# OledAdapter.net
KiCad netlist of a schematic drawn in EAGLE
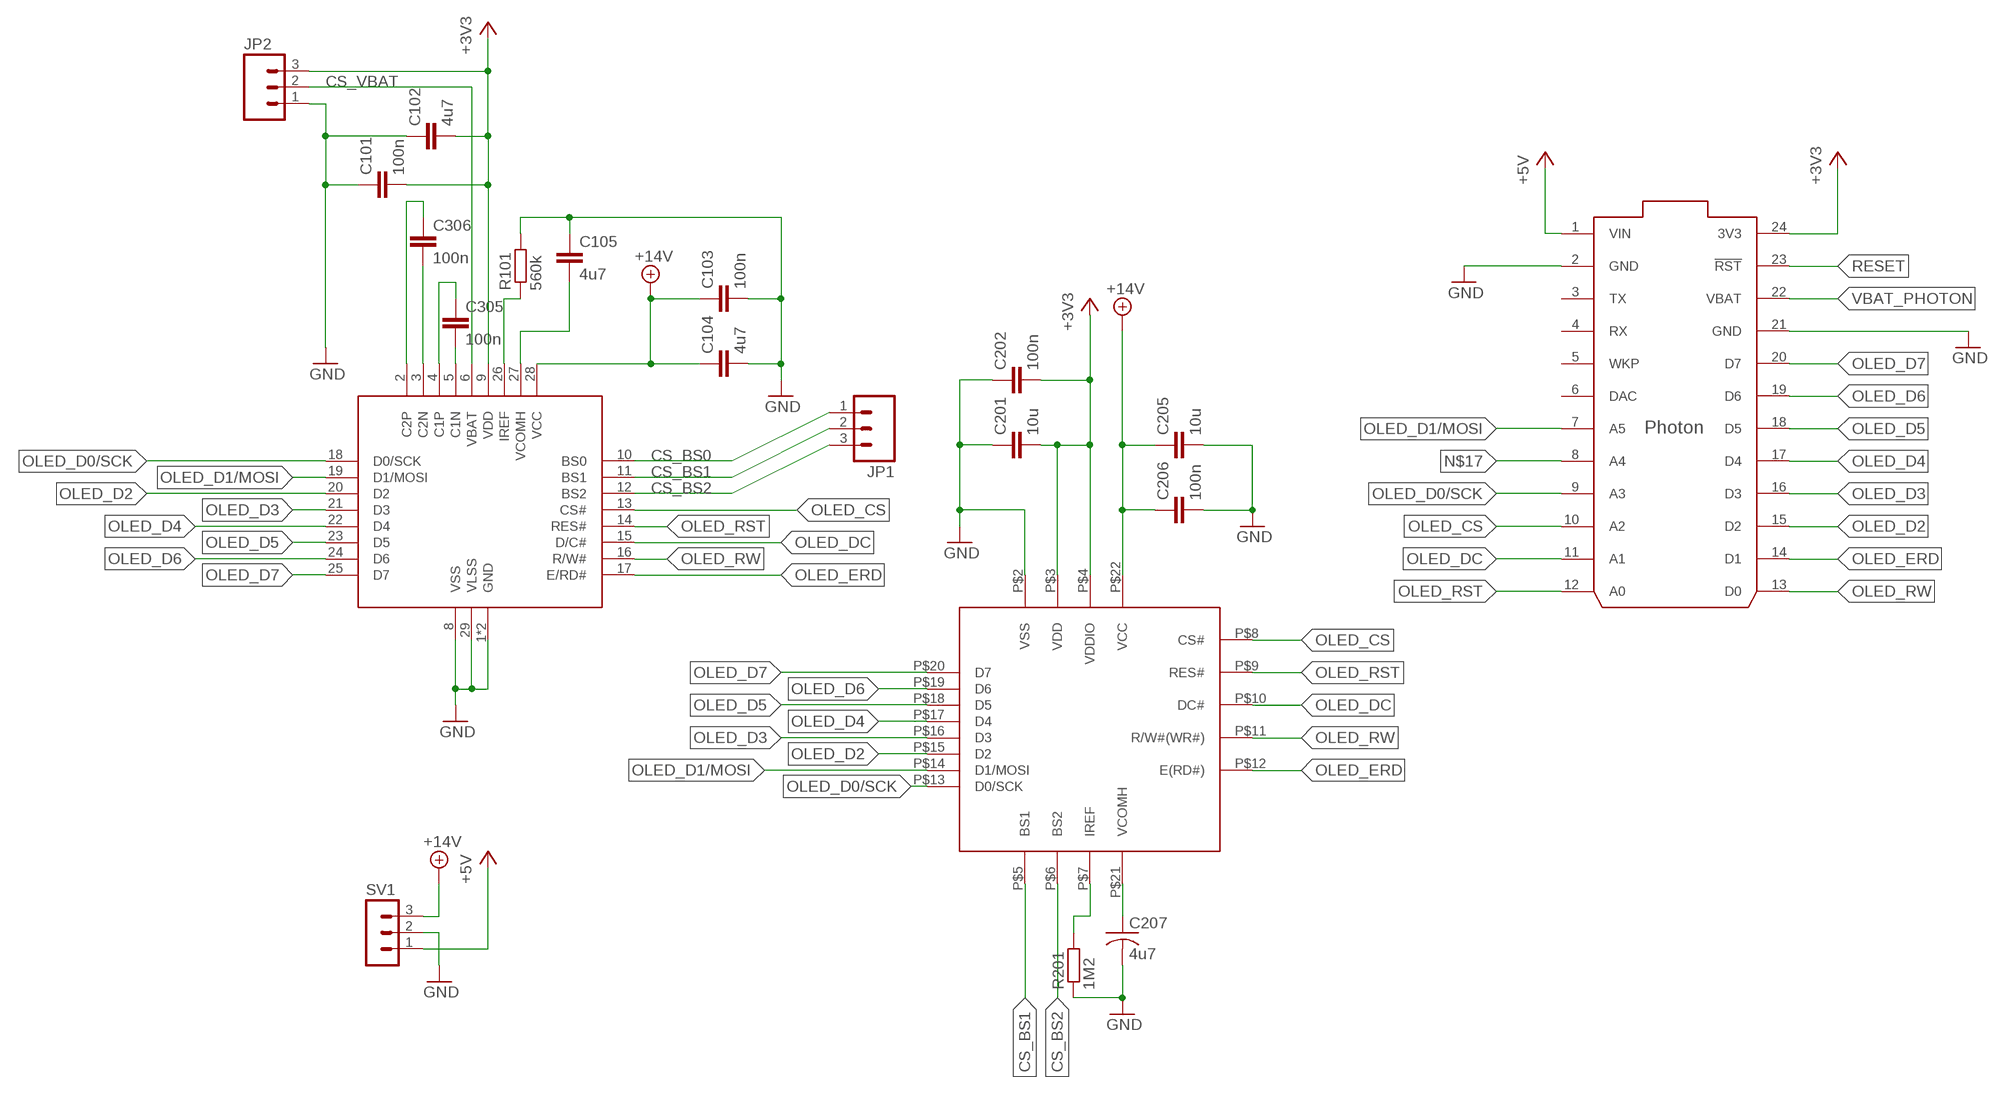
[diagram p0: schematic, sheet 1]

(export (version "E")
  (design (tool "Eeschema 10.0.6"))
  (components
    (comp (ref "C101")
      (value "100n")
      (footprint "eagle-import:C0603")
      (libsource (lib "eagle-import") (part "C-EUC0603"))
    )
    (comp (ref "C102")
      (value "4u7")
      (footprint "eagle-import:C0603")
      (libsource (lib "eagle-import") (part "C-EUC0603"))
    )
    (comp (ref "C103")
      (value "100n")
      (footprint "eagle-import:C0603")
      (libsource (lib "eagle-import") (part "C-EUC0603"))
    )
    (comp (ref "C104")
      (value "4u7")
      (footprint "eagle-import:C0603")
      (libsource (lib "eagle-import") (part "C-EUC0603"))
    )
    (comp (ref "C105")
      (value "4u7")
      (footprint "eagle-import:C0603")
      (libsource (lib "eagle-import") (part "C-EUC0603"))
    )
    (comp (ref "C201")
      (value "10u")
      (footprint "eagle-import:C0603")
      (libsource (lib "eagle-import") (part "C-EUC0603"))
    )
    (comp (ref "C202")
      (value "100n")
      (footprint "eagle-import:C0603")
      (libsource (lib "eagle-import") (part "C-EUC0603"))
    )
    (comp (ref "C205")
      (value "10u")
      (footprint "eagle-import:C0603")
      (libsource (lib "eagle-import") (part "C-EUC0603"))
    )
    (comp (ref "C206")
      (value "100n")
      (footprint "eagle-import:C0603")
      (libsource (lib "eagle-import") (part "C-EUC0603"))
    )
    (comp (ref "C207")
      (value "4u7")
      (footprint "eagle-import:C0603")
      (libsource (lib "eagle-import") (part "C-USC0603"))
    )
    (comp (ref "C305")
      (value "100n")
      (footprint "eagle-import:C0603")
      (libsource (lib "eagle-import") (part "C-EUC0603"))
    )
    (comp (ref "C306")
      (value "100n")
      (footprint "eagle-import:C0603")
      (libsource (lib "eagle-import") (part "C-EUC0603"))
    )
    (comp (ref "JP1")
      (value "M03PTH")
      (footprint "eagle-import:1X03")
      (libsource (lib "eagle-import") (part "M03PTH"))
    )
    (comp (ref "JP2")
      (value "M03PTH")
      (footprint "eagle-import:1X03")
      (libsource (lib "eagle-import") (part "M03PTH"))
    )
    (comp (ref "R101")
      (value "560k")
      (footprint "eagle-import:R0603")
      (libsource (lib "eagle-import") (part "R-EU_R0603"))
    )
    (comp (ref "R201")
      (value "1M2")
      (footprint "eagle-import:R0603")
      (libsource (lib "eagle-import") (part "R-EU_R0603"))
    )
    (comp (ref "SV1")
      (value "MA03-1")
      (footprint "eagle-import:MA03-1")
      (libsource (lib "eagle-import") (part "MA03-1"))
    )
    (comp (ref "U$1")
      (value "MCOT128064NZ-YM")
      (footprint "eagle-import:MCOT128064NZ-YM")
      (libsource (lib "eagle-import") (part "MCOT128064NZ-YM"))
    )
    (comp (ref "U$2")
      (value "PHOTON_WITH_HEADERS")
      (footprint "eagle-import:PHOTON")
      (libsource (lib "eagle-import") (part "PHOTON_WITH_HEADERS"))
    )
    (comp (ref "U$3")
      (value "MCOT096064AZ-RGBM")
      (footprint "eagle-import:MCOT096064AZ-RGBM")
      (libsource (lib "eagle-import") (part "MCOT096064AZ-RGBM"))
    )
  )
  (nets
    (net (code "1") (name "+3V3") (class "Default")
      (node (ref "C101") (pin "2") (pinfunction "2_2") (pintype "passive"))
      (node (ref "C102") (pin "2") (pinfunction "2_2") (pintype "passive"))
      (node (ref "C201") (pin "2") (pinfunction "2_2") (pintype "passive"))
      (node (ref "C202") (pin "2") (pinfunction "2_2") (pintype "passive"))
      (node (ref "JP2") (pin "3") (pinfunction "3_3") (pintype "passive"))
      (node (ref "U$1") (pin "9") (pinfunction "VDD_9") (pintype "power_in"))
      (node (ref "U$2") (pin "24") (pinfunction "3V3_24") (pintype "power_in"))
      (node (ref "U$3") (pin "P$3") (pinfunction "VDD_P$3") (pintype "bidirectional"))
      (node (ref "U$3") (pin "P$4") (pinfunction "VDDIO_P$4") (pintype "bidirectional"))
    )
    (net (code "2") (name "+5V") (class "Default")
      (node (ref "SV1") (pin "1") (pinfunction "1_1") (pintype "passive"))
      (node (ref "U$2") (pin "1") (pinfunction "VIN_1") (pintype "power_in"))
    )
    (net (code "3") (name "+14V") (class "Default")
      (node (ref "C103") (pin "1") (pinfunction "1_1") (pintype "passive"))
      (node (ref "C104") (pin "1") (pinfunction "1_1") (pintype "passive"))
      (node (ref "C205") (pin "1") (pinfunction "1_1") (pintype "passive"))
      (node (ref "C206") (pin "1") (pinfunction "1_1") (pintype "passive"))
      (node (ref "SV1") (pin "3") (pinfunction "3_3") (pintype "passive"))
      (node (ref "U$1") (pin "28") (pinfunction "VCC_28") (pintype "power_in"))
      (node (ref "U$3") (pin "P$22") (pinfunction "VCC_P$22") (pintype "bidirectional"))
    )
    (net (code "4") (name "/CS_BS0") (class "Default")
      (node (ref "JP1") (pin "1") (pinfunction "1_1") (pintype "passive"))
      (node (ref "U$1") (pin "10") (pinfunction "BS0_10") (pintype "bidirectional"))
    )
    (net (code "5") (name "/CS_VBAT") (class "Default")
      (node (ref "JP2") (pin "2") (pinfunction "2_2") (pintype "passive"))
      (node (ref "U$1") (pin "6") (pinfunction "VBAT_6") (pintype "power_in"))
    )
    (net (code "6") (name "CS_BS1") (class "Default")
      (node (ref "JP1") (pin "2") (pinfunction "2_2") (pintype "passive"))
      (node (ref "U$1") (pin "11") (pinfunction "BS1_11") (pintype "bidirectional"))
      (node (ref "U$3") (pin "P$5") (pinfunction "BS1_P$5") (pintype "bidirectional"))
    )
    (net (code "7") (name "CS_BS2") (class "Default")
      (node (ref "JP1") (pin "3") (pinfunction "3_3") (pintype "passive"))
      (node (ref "U$1") (pin "12") (pinfunction "BS2_12") (pintype "bidirectional"))
      (node (ref "U$3") (pin "P$6") (pinfunction "BS2_P$6") (pintype "bidirectional"))
    )
    (net (code "8") (name "GND") (class "Default")
      (node (ref "C101") (pin "1") (pinfunction "1_1") (pintype "passive"))
      (node (ref "C102") (pin "1") (pinfunction "1_1") (pintype "passive"))
      (node (ref "C103") (pin "2") (pinfunction "2_2") (pintype "passive"))
      (node (ref "C104") (pin "2") (pinfunction "2_2") (pintype "passive"))
      (node (ref "C105") (pin "1") (pinfunction "1_1") (pintype "passive"))
      (node (ref "C201") (pin "1") (pinfunction "1_1") (pintype "passive"))
      (node (ref "C202") (pin "1") (pinfunction "1_1") (pintype "passive"))
      (node (ref "C205") (pin "2") (pinfunction "2_2") (pintype "passive"))
      (node (ref "C206") (pin "2") (pinfunction "2_2") (pintype "passive"))
      (node (ref "C207") (pin "2") (pinfunction "2_2") (pintype "passive"))
      (node (ref "JP2") (pin "1") (pinfunction "1_1") (pintype "passive"))
      (node (ref "R101") (pin "2") (pinfunction "2_2") (pintype "passive"))
      (node (ref "R201") (pin "1") (pinfunction "1_1") (pintype "passive"))
      (node (ref "SV1") (pin "2") (pinfunction "2_2") (pintype "passive"))
      (node (ref "U$1") (pin "1") (pinfunction "GND_1") (pintype "power_in"))
      (node (ref "U$1") (pin "29") (pinfunction "VLSS_29") (pintype "power_in"))
      (node (ref "U$1") (pin "30") (pinfunction "GND_30") (pintype "power_in"))
      (node (ref "U$1") (pin "8") (pinfunction "VSS_8") (pintype "power_in"))
      (node (ref "U$2") (pin "2") (pinfunction "GND_2") (pintype "power_in"))
      (node (ref "U$2") (pin "21") (pinfunction "GND_21") (pintype "power_in"))
      (node (ref "U$3") (pin "P$2") (pinfunction "VSS_P$2") (pintype "bidirectional"))
    )
    (net (code "9") (name "N$17") (class "Default")
      (node (ref "U$2") (pin "8") (pinfunction "A4_8") (pintype "bidirectional"))
    )
    (net (code "10") (name "Net-(U$1-C1N)") (class "Default")
      (node (ref "C305") (pin "2") (pinfunction "2_2") (pintype "passive"))
      (node (ref "U$1") (pin "5") (pinfunction "C1N_5") (pintype "bidirectional"))
    )
    (net (code "11") (name "Net-(U$1-C1P)") (class "Default")
      (node (ref "C305") (pin "1") (pinfunction "1_1") (pintype "passive"))
      (node (ref "U$1") (pin "4") (pinfunction "C1P_4") (pintype "bidirectional"))
    )
    (net (code "12") (name "Net-(U$1-C2N)") (class "Default")
      (node (ref "C306") (pin "2") (pinfunction "2_2") (pintype "passive"))
      (node (ref "U$1") (pin "3") (pinfunction "C2N_3") (pintype "bidirectional"))
    )
    (net (code "13") (name "Net-(U$1-C2P)") (class "Default")
      (node (ref "C306") (pin "1") (pinfunction "1_1") (pintype "passive"))
      (node (ref "U$1") (pin "2") (pinfunction "C2P_2") (pintype "bidirectional"))
    )
    (net (code "14") (name "Net-(U$1-IREF)") (class "Default")
      (node (ref "R101") (pin "1") (pinfunction "1_1") (pintype "passive"))
      (node (ref "U$1") (pin "26") (pinfunction "IREF_26") (pintype "bidirectional"))
    )
    (net (code "15") (name "Net-(U$1-VCOMH)") (class "Default")
      (node (ref "C105") (pin "2") (pinfunction "2_2") (pintype "passive"))
      (node (ref "U$1") (pin "27") (pinfunction "VCOMH_27") (pintype "bidirectional"))
    )
    (net (code "16") (name "Net-(U$3-IREF)") (class "Default")
      (node (ref "R201") (pin "2") (pinfunction "2_2") (pintype "passive"))
      (node (ref "U$3") (pin "P$7") (pinfunction "IREF_P$7") (pintype "bidirectional"))
    )
    (net (code "17") (name "Net-(U$3-VCOMH)") (class "Default")
      (node (ref "C207") (pin "1") (pinfunction "1_1") (pintype "passive"))
      (node (ref "U$3") (pin "P$21") (pinfunction "VCOMH_P$21") (pintype "bidirectional"))
    )
    (net (code "18") (name "OLED_CS") (class "Default")
      (node (ref "U$1") (pin "13") (pinfunction "CS#_13") (pintype "bidirectional"))
      (node (ref "U$2") (pin "10") (pinfunction "A2_10") (pintype "bidirectional"))
      (node (ref "U$3") (pin "P$8") (pinfunction "CS#_P$8") (pintype "bidirectional"))
    )
    (net (code "19") (name "OLED_D0{slash}SCK") (class "Default")
      (node (ref "U$1") (pin "18") (pinfunction "D0/SCK_18") (pintype "bidirectional"))
      (node (ref "U$2") (pin "9") (pinfunction "A3_9") (pintype "bidirectional"))
      (node (ref "U$3") (pin "P$13") (pinfunction "D0/SCK_P$13") (pintype "bidirectional"))
    )
    (net (code "20") (name "OLED_D1{slash}MOSI") (class "Default")
      (node (ref "U$1") (pin "19") (pinfunction "D1/MOSI_19") (pintype "bidirectional"))
      (node (ref "U$2") (pin "7") (pinfunction "A5_7") (pintype "bidirectional"))
      (node (ref "U$3") (pin "P$14") (pinfunction "D1/MOSI_P$14") (pintype "bidirectional"))
    )
    (net (code "21") (name "OLED_D2") (class "Default")
      (node (ref "U$1") (pin "20") (pinfunction "D2_20") (pintype "bidirectional"))
      (node (ref "U$2") (pin "15") (pinfunction "D2_15") (pintype "bidirectional"))
      (node (ref "U$3") (pin "P$15") (pinfunction "D2_P$15") (pintype "bidirectional"))
    )
    (net (code "22") (name "OLED_D3") (class "Default")
      (node (ref "U$1") (pin "21") (pinfunction "D3_21") (pintype "bidirectional"))
      (node (ref "U$2") (pin "16") (pinfunction "D3_16") (pintype "bidirectional"))
      (node (ref "U$3") (pin "P$16") (pinfunction "D3_P$16") (pintype "bidirectional"))
    )
    (net (code "23") (name "OLED_D4") (class "Default")
      (node (ref "U$1") (pin "22") (pinfunction "D4_22") (pintype "bidirectional"))
      (node (ref "U$2") (pin "17") (pinfunction "D4_17") (pintype "bidirectional"))
      (node (ref "U$3") (pin "P$17") (pinfunction "D4_P$17") (pintype "bidirectional"))
    )
    (net (code "24") (name "OLED_D5") (class "Default")
      (node (ref "U$1") (pin "23") (pinfunction "D5_23") (pintype "bidirectional"))
      (node (ref "U$2") (pin "18") (pinfunction "D5_18") (pintype "bidirectional"))
      (node (ref "U$3") (pin "P$18") (pinfunction "D5_P$18") (pintype "bidirectional"))
    )
    (net (code "25") (name "OLED_D6") (class "Default")
      (node (ref "U$1") (pin "24") (pinfunction "D6_24") (pintype "bidirectional"))
      (node (ref "U$2") (pin "19") (pinfunction "D6_19") (pintype "bidirectional"))
      (node (ref "U$3") (pin "P$19") (pinfunction "D6_P$19") (pintype "bidirectional"))
    )
    (net (code "26") (name "OLED_D7") (class "Default")
      (node (ref "U$1") (pin "25") (pinfunction "D7_25") (pintype "bidirectional"))
      (node (ref "U$2") (pin "20") (pinfunction "D7_20") (pintype "bidirectional"))
      (node (ref "U$3") (pin "P$20") (pinfunction "D7_P$20") (pintype "bidirectional"))
    )
    (net (code "27") (name "OLED_DC") (class "Default")
      (node (ref "U$1") (pin "15") (pinfunction "D/C#_15") (pintype "bidirectional"))
      (node (ref "U$2") (pin "11") (pinfunction "A1_11") (pintype "bidirectional"))
      (node (ref "U$3") (pin "P$10") (pinfunction "DC#_P$10") (pintype "bidirectional"))
    )
    (net (code "28") (name "OLED_ERD") (class "Default")
      (node (ref "U$1") (pin "17") (pinfunction "E/RD#_17") (pintype "bidirectional"))
      (node (ref "U$2") (pin "14") (pinfunction "D1_14") (pintype "bidirectional"))
      (node (ref "U$3") (pin "P$12") (pinfunction "E(RD#)_P$12") (pintype "bidirectional"))
    )
    (net (code "29") (name "OLED_RST") (class "Default")
      (node (ref "U$1") (pin "14") (pinfunction "RES#_14") (pintype "bidirectional"))
      (node (ref "U$2") (pin "12") (pinfunction "A0_12") (pintype "bidirectional"))
      (node (ref "U$3") (pin "P$9") (pinfunction "RES#_P$9") (pintype "bidirectional"))
    )
    (net (code "30") (name "OLED_RW") (class "Default")
      (node (ref "U$1") (pin "16") (pinfunction "R/W#_16") (pintype "bidirectional"))
      (node (ref "U$2") (pin "13") (pinfunction "D0_13") (pintype "bidirectional"))
      (node (ref "U$3") (pin "P$11") (pinfunction "R/W#(WR#)_P$11") (pintype "bidirectional"))
    )
    (net (code "31") (name "RESET") (class "Default")
      (node (ref "U$2") (pin "23") (pinfunction "~{RST}_23") (pintype "bidirectional"))
    )
    (net (code "32") (name "VBAT_PHOTON") (class "Default")
      (node (ref "U$2") (pin "22") (pinfunction "VBAT_22") (pintype "power_in"))
    )
    (net (code "33") (name "unconnected-(U$2-DAC-Pad6)") (class "Default")
      (node (ref "U$2") (pin "6") (pinfunction "DAC_6") (pintype "bidirectional"))
    )
    (net (code "34") (name "unconnected-(U$2-RX-Pad4)") (class "Default")
      (node (ref "U$2") (pin "4") (pinfunction "RX_4") (pintype "bidirectional"))
    )
    (net (code "35") (name "unconnected-(U$2-TX-Pad3)") (class "Default")
      (node (ref "U$2") (pin "3") (pinfunction "TX_3") (pintype "bidirectional"))
    )
    (net (code "36") (name "unconnected-(U$2-WKP-Pad5)") (class "Default")
      (node (ref "U$2") (pin "5") (pinfunction "WKP_5") (pintype "bidirectional"))
    )
  )
)
